# SCH_fig1_2021-11-24.net
KiCad netlist of a schematic drawn in EasyEDA
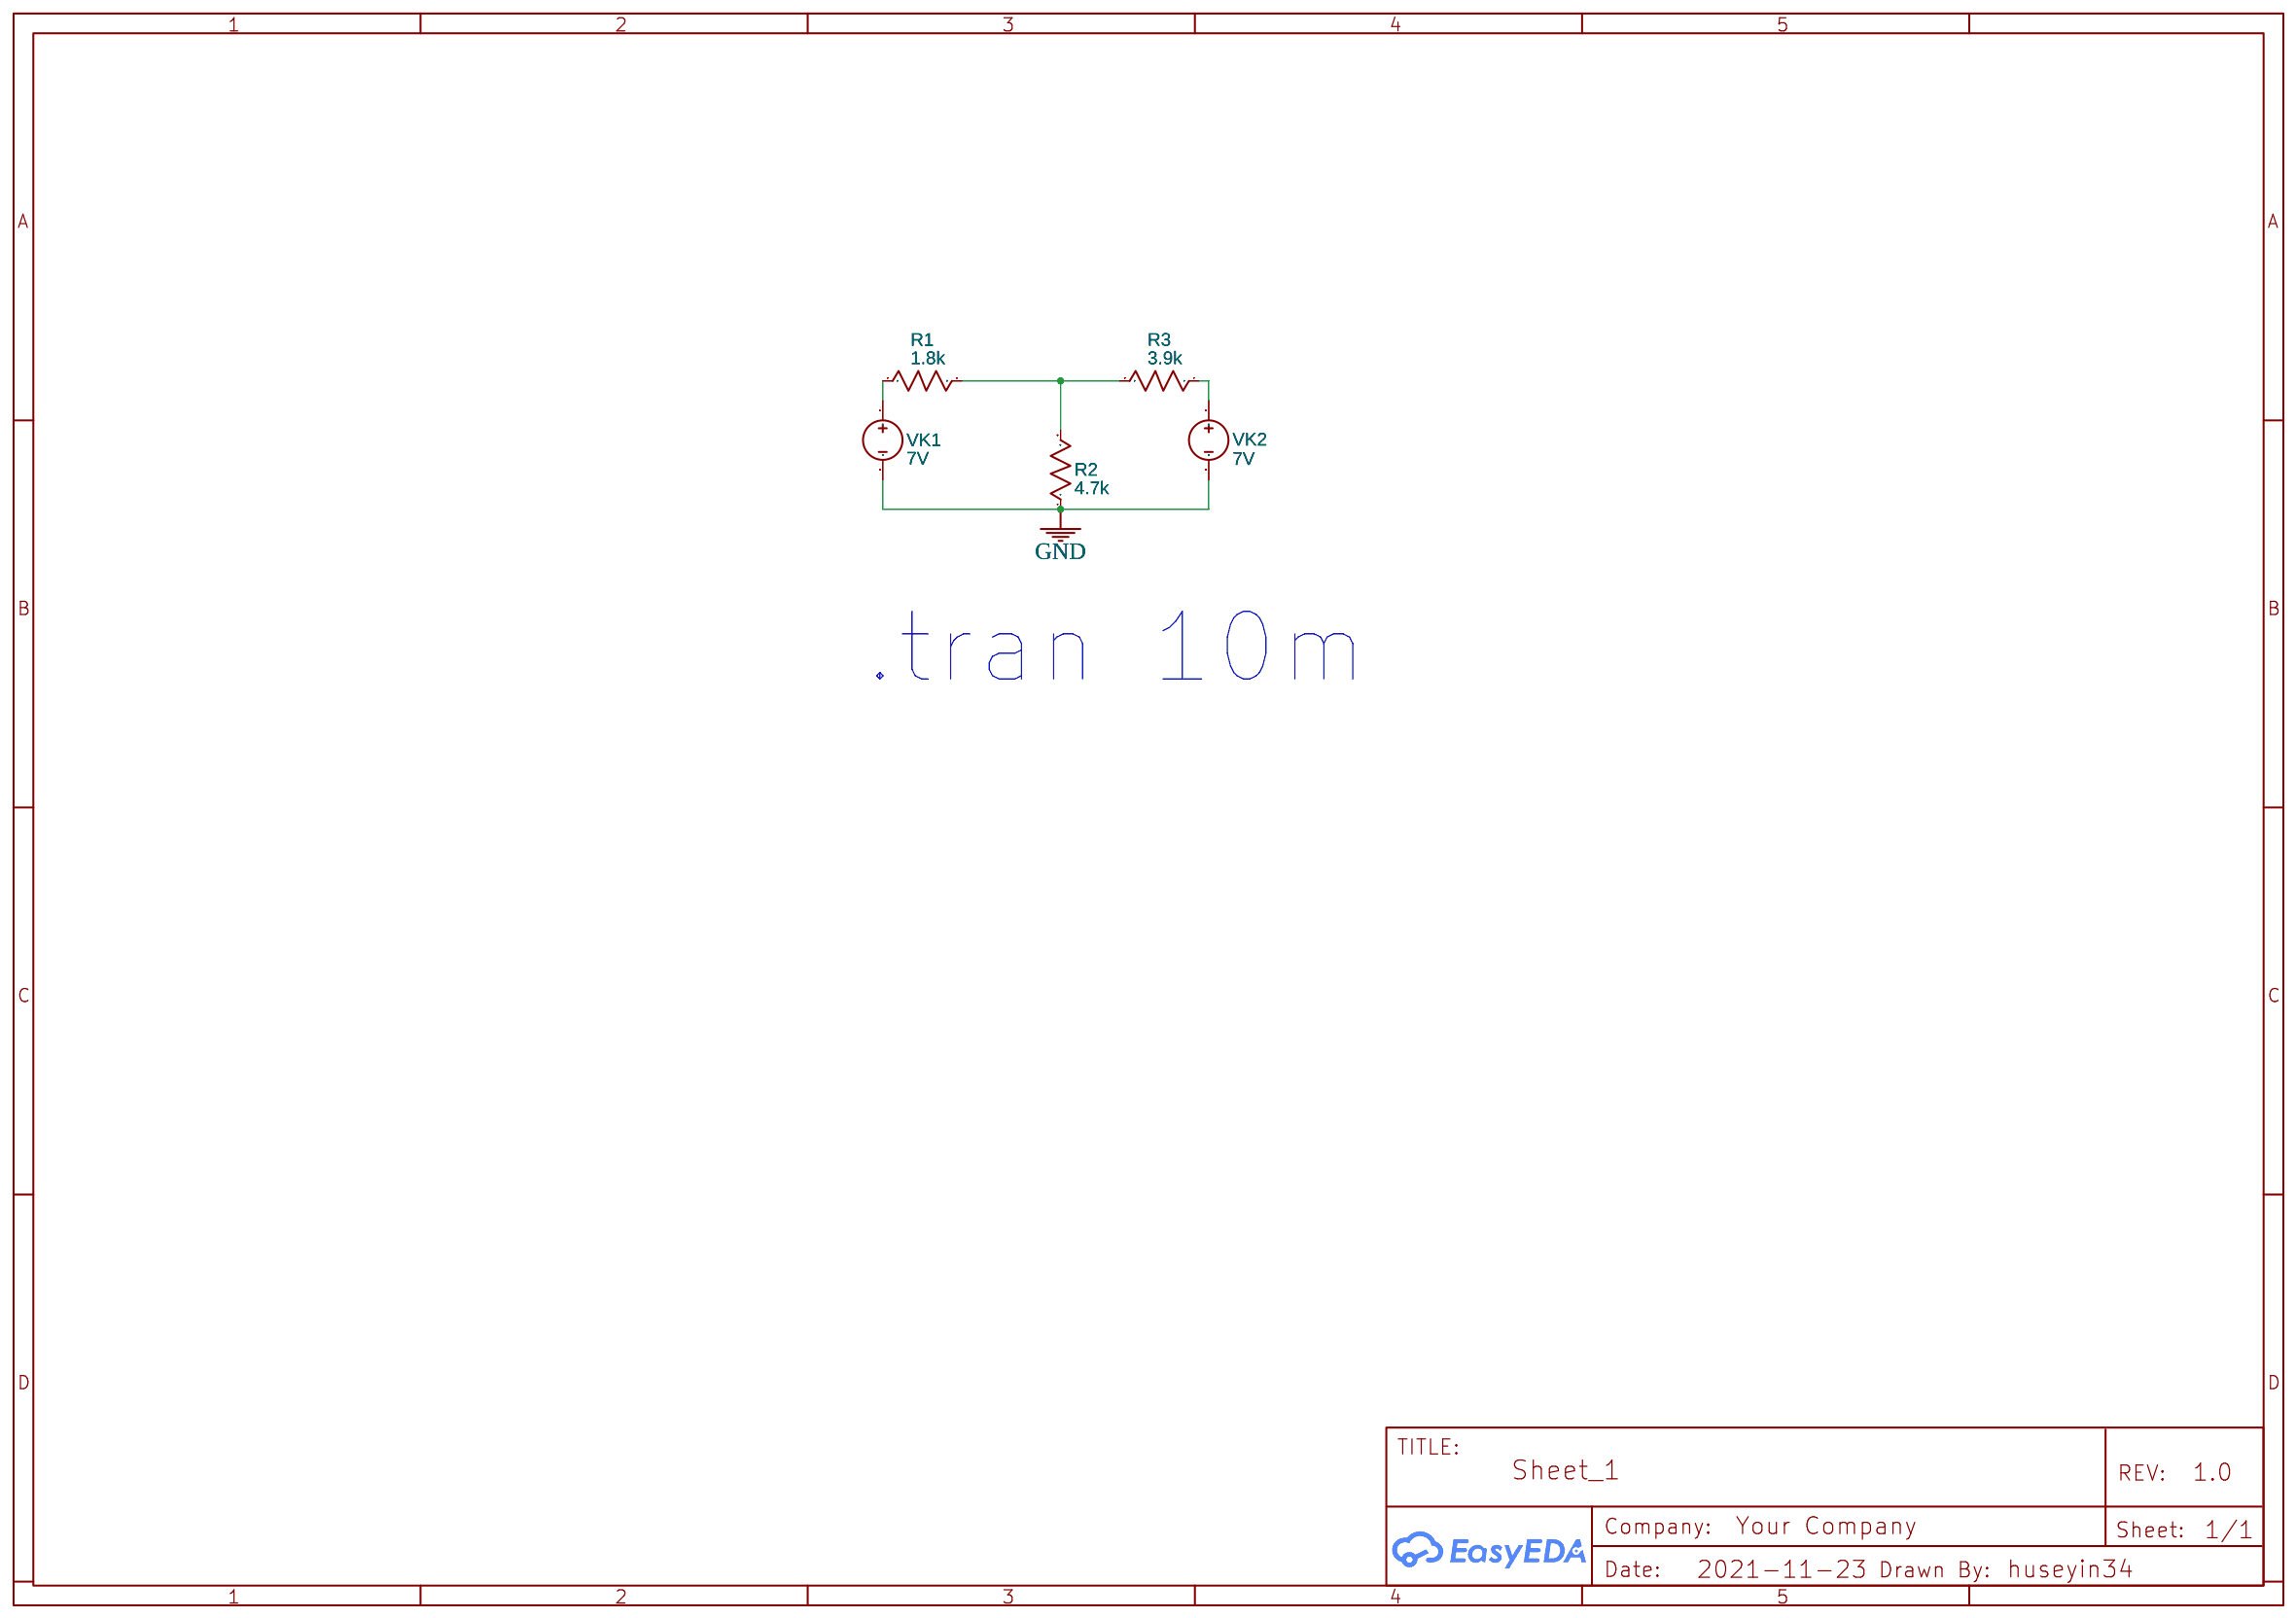
[diagram p0: schematic sheet]

(export (version "E")
  (design (tool "Eeschema 10.0.6"))
  (components
    (comp (ref "R1") (value "1.8k") (libsource (lib "") (part "Resistor_US_1")))
    (comp (ref "R2") (value "4.7k") (libsource (lib "") (part "Resistor_US_2")))
    (comp (ref "R3") (value "3.9k") (libsource (lib "") (part "Resistor_US")))
    (comp (ref "VK1") (value "7V") (libsource (lib "") (part "VDC")))
    (comp (ref "VK2") (value "7V") (libsource (lib "") (part "VDC")))
  )
  (nets
    (net (code "1") (name "GND") (class "Default")
      (node (ref "R2") (pin "1") (pinfunction "1_1") (pintype "unspecified"))
      (node (ref "VK1") (pin "2") (pinfunction "2_2") (pintype "unspecified"))
      (node (ref "VK2") (pin "2") (pinfunction "2_2") (pintype "unspecified"))
    )
    (net (code "2") (name "Net-(R1-Pad1)") (class "Default")
      (node (ref "R1") (pin "1") (pinfunction "1_1") (pintype "unspecified"))
      (node (ref "VK1") (pin "1") (pinfunction "1_1") (pintype "unspecified"))
    )
    (net (code "3") (name "Net-(R1-Pad2)") (class "Default")
      (node (ref "R1") (pin "2") (pinfunction "2_2") (pintype "unspecified"))
      (node (ref "R2") (pin "2") (pinfunction "2_2") (pintype "unspecified"))
      (node (ref "R3") (pin "2") (pinfunction "2_2") (pintype "unspecified"))
    )
    (net (code "4") (name "Net-(R3-Pad1)") (class "Default")
      (node (ref "R3") (pin "1") (pinfunction "1_1") (pintype "unspecified"))
      (node (ref "VK2") (pin "1") (pinfunction "1_1") (pintype "unspecified"))
    )
  )
)
